# SCH_PCB-Hacker-Card_2024-07-17.net
KiCad netlist of a schematic drawn in EasyEDA
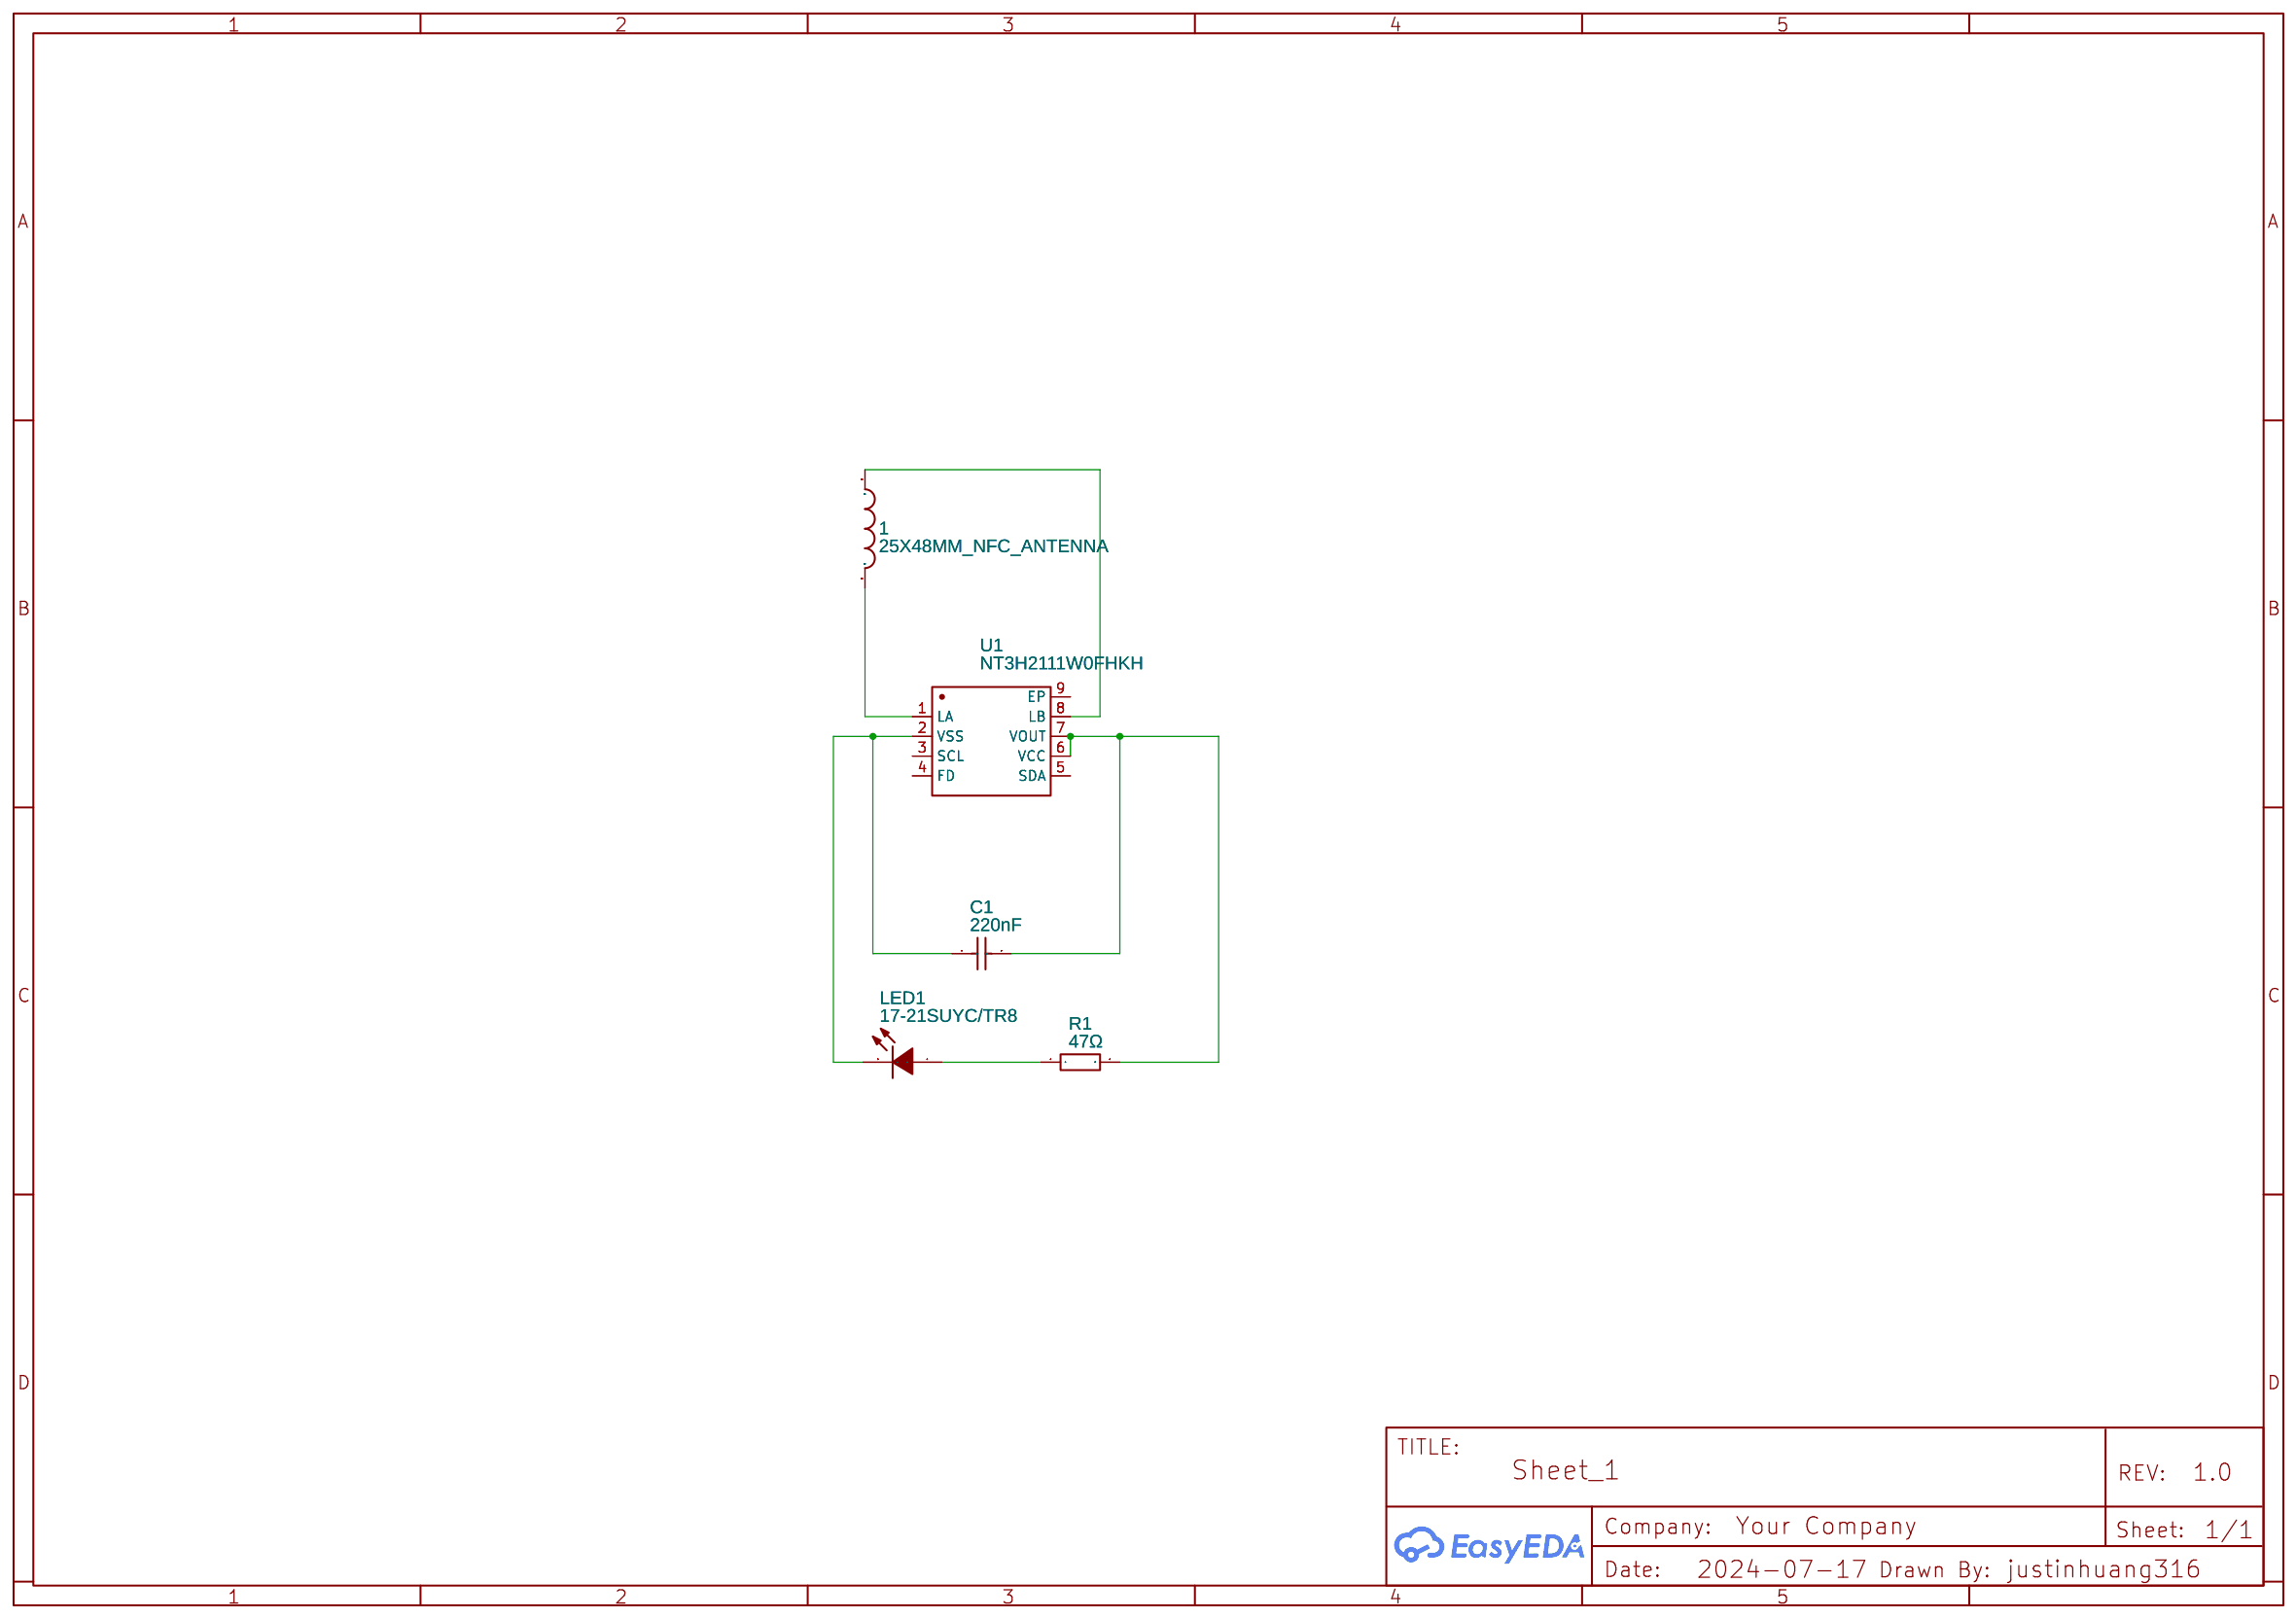
[diagram p0: schematic sheet]

(export (version "E")
  (design (tool "Eeschema 10.0.6"))
  (components
    (comp (ref "1") (value "25X48MM_NFC_ANTENNA") (libsource (lib "") (part "25X48MM_NFC_ANTENNA")))
    (comp (ref "C1")
      (value "220nF")
      (fields
        (field (name "Manufacturer Part") "CL10B224KA8NNNC")
        (field (name "Manufacturer") "SAMSUNG(三星)")
      )
      (libsource (lib "") (part "CL10B224KA8NNNC"))
    )
    (comp (ref "LED1")
      (value "17-21SUYC/TR8")
      (fields (field (name "Manufacturer Part") "KT-0805黄灯") (field (name "Manufacturer") "KENTO"))
      (libsource (lib "") (part "17-21SUYC/TR8"))
    )
    (comp (ref "R1")
      (value "47Ω")
      (fields
        (field (name "Manufacturer Part") "0603WAF470JT5E")
        (field (name "Manufacturer") "UNI-ROYAL(厚声)")
      )
      (libsource (lib "") (part "0603WAF470JT5E"))
    )
    (comp (ref "U1")
      (value "NT3H2111W0FHKH")
      (fields (field (name "Manufacturer") "NXP(恩智浦)"))
      (libsource (lib "") (part "NT3H2111W0FHKH"))
    )
  )
  (nets
    (net (code "1") (name "Net-(LED1-+)") (class "Default")
      (node (ref "LED1") (pin "1") (pinfunction "+_1") (pintype "unspecified"))
      (node (ref "R1") (pin "1") (pinfunction "1_1") (pintype "input"))
    )
    (net (code "2") (name "Net-(LED1--)") (class "Default")
      (node (ref "C1") (pin "1") (pinfunction "1_1") (pintype "input"))
      (node (ref "LED1") (pin "2") (pinfunction "-_2") (pintype "unspecified"))
      (node (ref "U1") (pin "2") (pinfunction "VSS_2") (pintype "unspecified"))
    )
    (net (code "3") (name "Net-(U1-LA)") (class "Default")
      (node (ref "1") (pin "P$2") (pinfunction "P$2_P$2") (pintype "bidirectional"))
      (node (ref "U1") (pin "1") (pinfunction "LA_1") (pintype "unspecified"))
    )
    (net (code "4") (name "Net-(U1-LB)") (class "Default")
      (node (ref "1") (pin "P$1") (pinfunction "P$1_P$1") (pintype "bidirectional"))
      (node (ref "U1") (pin "8") (pinfunction "LB_8") (pintype "unspecified"))
    )
    (net (code "5") (name "Net-(U1-VCC)") (class "Default")
      (node (ref "C1") (pin "2") (pinfunction "2_2") (pintype "input"))
      (node (ref "R1") (pin "2") (pinfunction "2_2") (pintype "input"))
      (node (ref "U1") (pin "6") (pinfunction "VCC_6") (pintype "unspecified"))
      (node (ref "U1") (pin "7") (pinfunction "VOUT_7") (pintype "unspecified"))
    )
    (net (code "6") (name "unconnected-(U1-EP-Pad9)") (class "Default")
      (node (ref "U1") (pin "9") (pinfunction "EP_9") (pintype "unspecified"))
    )
    (net (code "7") (name "unconnected-(U1-FD-Pad4)") (class "Default")
      (node (ref "U1") (pin "4") (pinfunction "FD_4") (pintype "unspecified"))
    )
    (net (code "8") (name "unconnected-(U1-SCL-Pad3)") (class "Default")
      (node (ref "U1") (pin "3") (pinfunction "SCL_3") (pintype "unspecified"))
    )
    (net (code "9") (name "unconnected-(U1-SDA-Pad5)") (class "Default")
      (node (ref "U1") (pin "5") (pinfunction "SDA_5") (pintype "unspecified"))
    )
  )
)
